# CH32V467VET-R0.net
KiCad netlist of a schematic drawn in Altium Designer
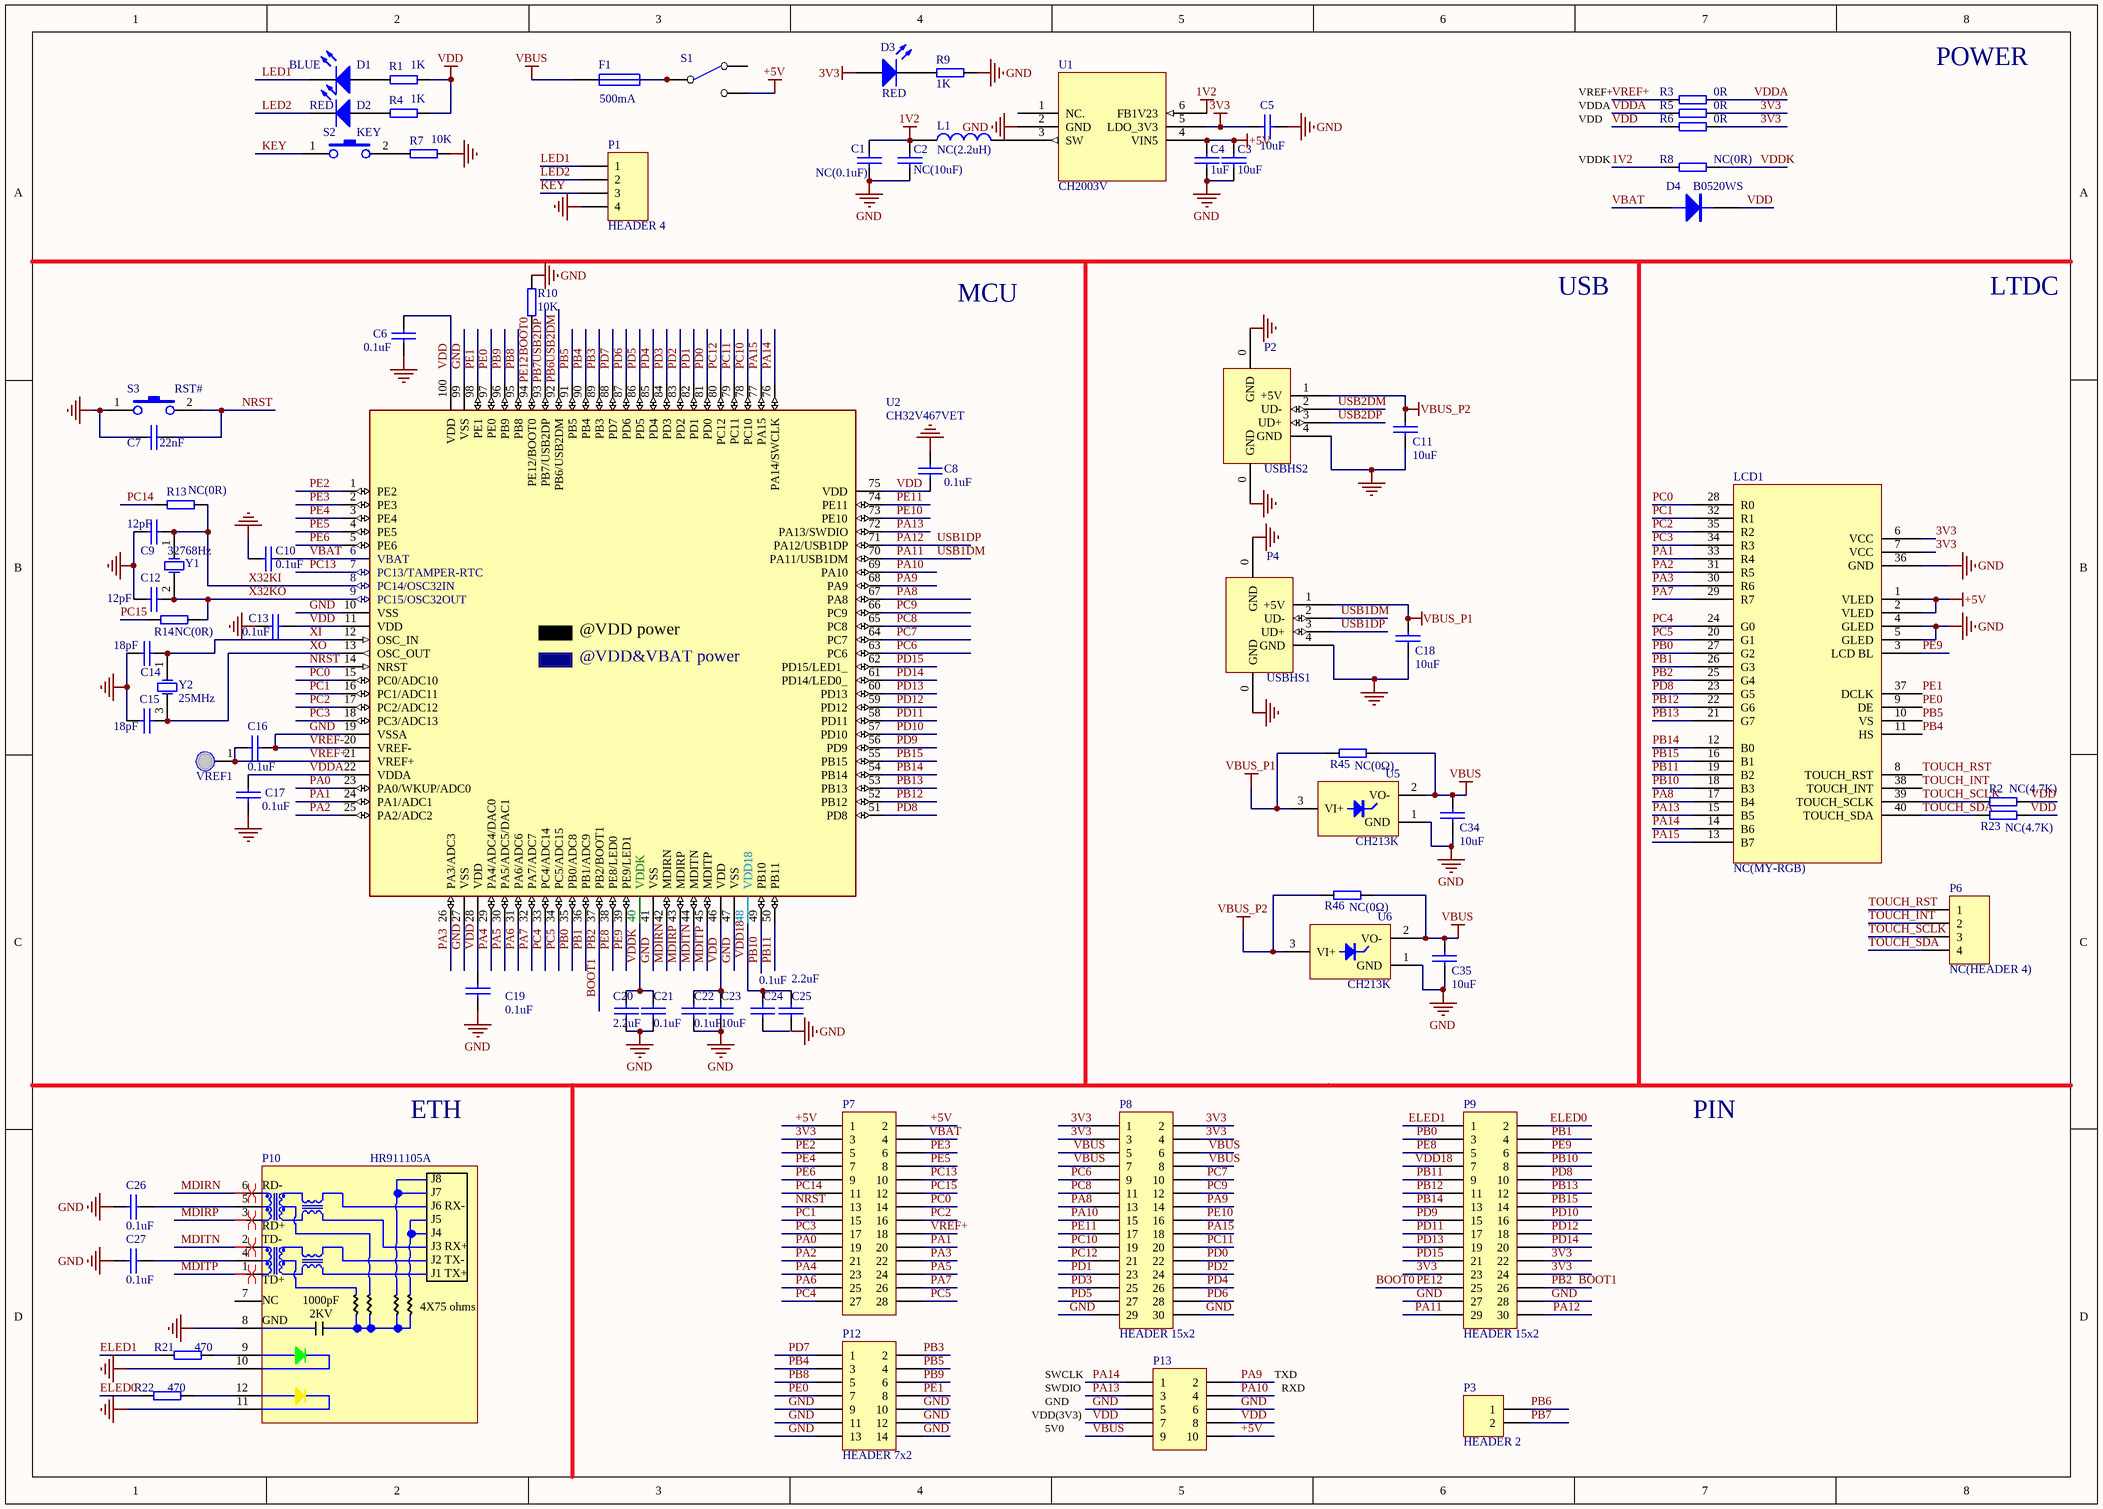
[diagram p0: CH32V467VET-R0.SchDoc]

(export (version "E")
  (design (tool "Eeschema 10.0.6"))
  (components
    (comp (ref "C1")
      (value "NC(0.1uF)")
      (footprint "0402_C")
      (description "Capacitor")
      (libsource (lib "") (part "CAP_1"))
    )
    (comp (ref "C2")
      (value "NC(10uF)")
      (footprint "0603_C")
      (description "Capacitor")
      (libsource (lib "*") (part "CAP"))
    )
    (comp (ref "C3")
      (value "10uF")
      (footprint "0603_C")
      (description "Capacitor")
      (libsource (lib "*") (part "CAP"))
    )
    (comp (ref "C4")
      (value "1uF")
      (footprint "0402_C")
      (description "Capacitor")
      (libsource (lib "") (part "CAP_1"))
    )
    (comp (ref "C5")
      (value "10uF")
      (footprint "0603_C")
      (description "Capacitor")
      (libsource (lib "*") (part "CAP"))
    )
    (comp (ref "C6")
      (value "0.1uF")
      (footprint "0402_C")
      (description "Capacitor")
      (libsource (lib "*") (part "CAP"))
    )
    (comp (ref "C7")
      (value "22nF")
      (footprint "0402_C")
      (description "Capacitor")
      (libsource (lib "") (part "CAP_2"))
    )
    (comp (ref "C8")
      (value "0.1uF")
      (footprint "0402_C")
      (description "Capacitor")
      (libsource (lib "*") (part "CAP"))
    )
    (comp (ref "C9")
      (value "12pF")
      (footprint "0402_C")
      (description "Capacitor")
      (libsource (lib "*") (part "CAP"))
    )
    (comp (ref "C10")
      (value "0.1uF")
      (footprint "0402_C")
      (description "Capacitor")
      (libsource (lib "*") (part "CAP"))
    )
    (comp (ref "C11")
      (value "10uF")
      (footprint "0603_C")
      (description "Capacitor")
      (libsource (lib "") (part "CAP_2"))
    )
    (comp (ref "C12")
      (value "12pF")
      (footprint "0402_C")
      (description "Capacitor")
      (libsource (lib "*") (part "CAP"))
    )
    (comp (ref "C13")
      (value "0.1uF")
      (footprint "0402_C")
      (description "Capacitor")
      (libsource (lib "*") (part "CAP"))
    )
    (comp (ref "C14")
      (value "18pF")
      (footprint "0402_C")
      (description "Capacitor")
      (libsource (lib "*") (part "CAP"))
    )
    (comp (ref "C15")
      (value "18pF")
      (footprint "0402_C")
      (description "Capacitor")
      (libsource (lib "*") (part "CAP"))
    )
    (comp (ref "C16")
      (value "0.1uF")
      (footprint "0402_C")
      (description "Capacitor")
      (libsource (lib "*") (part "CAP"))
    )
    (comp (ref "C17")
      (value "0.1uF")
      (footprint "0402_C")
      (description "Capacitor")
      (libsource (lib "*") (part "CAP"))
    )
    (comp (ref "C18")
      (value "10uF")
      (footprint "0603_C")
      (description "Capacitor")
      (libsource (lib "") (part "CAP_2"))
    )
    (comp (ref "C19")
      (value "0.1uF")
      (footprint "0402_C")
      (description "Capacitor")
      (libsource (lib "*") (part "CAP"))
    )
    (comp (ref "C20")
      (value "2.2uF")
      (footprint "0402_C")
      (description "Capacitor")
      (libsource (lib "*") (part "CAP"))
    )
    (comp (ref "C21")
      (value "0.1uF")
      (footprint "0402_C")
      (description "Capacitor")
      (libsource (lib "*") (part "CAP"))
    )
    (comp (ref "C22")
      (value "0.1uF")
      (footprint "0402_C")
      (description "Capacitor")
      (libsource (lib "*") (part "CAP"))
    )
    (comp (ref "C23")
      (value "10uF")
      (footprint "0402_C")
      (description "Capacitor")
      (libsource (lib "*") (part "CAP"))
    )
    (comp (ref "C24")
      (value "0.1uF")
      (footprint "0402_C")
      (description "Capacitor")
      (libsource (lib "*") (part "CAP"))
    )
    (comp (ref "C25")
      (value "2.2uF")
      (footprint "0402_C")
      (description "Capacitor")
      (libsource (lib "*") (part "CAP"))
    )
    (comp (ref "C26")
      (value "0.1uF")
      (footprint "0402_C")
      (description "Capacitor")
      (libsource (lib "wch_sch_others") (part "CAP"))
    )
    (comp (ref "C27")
      (value "0.1uF")
      (footprint "0402_C")
      (description "Capacitor")
      (libsource (lib "wch_sch_others") (part "CAP"))
    )
    (comp (ref "C34")
      (value "10uF")
      (footprint "0603_C")
      (description "Capacitor")
      (libsource (lib "") (part "CAP_2"))
    )
    (comp (ref "C35")
      (value "10uF")
      (footprint "0603_C")
      (description "Capacitor")
      (libsource (lib "") (part "CAP_2"))
    )
    (comp (ref "D1")
      (value "BLUE")
      (footprint "0603+")
      (description "Typical INFRARED GaAs LED")
      (fields (field (name "PUBLISHER") "Altium Limited"))
      (libsource (lib "*") (part "LED0"))
    )
    (comp (ref "D2")
      (value "RED")
      (footprint "0603+")
      (description "Typical INFRARED GaAs LED")
      (fields (field (name "PUBLISHER") "Altium Limited"))
      (libsource (lib "*") (part "LED0"))
    )
    (comp (ref "D3")
      (value "RED")
      (footprint "0603+")
      (description "Typical INFRARED GaAs LED")
      (fields (field (name "PUBLISHER") "Altium Limited"))
      (libsource (lib "*") (part "LED0"))
    )
    (comp (ref "D4")
      (value "B0520WS")
      (footprint "SOD-323")
      (description "Diode")
      (libsource (lib "*") (part "DIODE"))
    )
    (comp (ref "F1")
      (value "500mA")
      (footprint "0603")
      (description "Fuse")
      (libsource (lib "wch_sch_others") (part "FUSE1"))
    )
    (comp (ref "L1") (value "NC(2.2uH)") (footprint "CD32") (libsource (lib "*") (part "INDUCTOR")))
    (comp (ref "LCD1")
      (value "NC(MY-RGB)")
      (footprint "FPC40P-0.5-FK750M3")
      (libsource (lib "MY-显示") (part "MY-RGB"))
    )
    (comp (ref "P1")
      (value "HEADER 4")
      (footprint "SIP4-2.54mm")
      (description "Header, 4-Pin")
      (libsource (lib "wch_sch_others") (part "HEADER 4"))
    )
    (comp (ref "P2")
      (value "USBHS2")
      (footprint "USBAF")
      (description "USB Port")
      (libsource (lib "*") (part "USB"))
    )
    (comp (ref "P3")
      (value "HEADER 2")
      (footprint "MYPCB:SIP2-2.54mm")
      (description "Header, 2-Pin")
      (libsource (lib "wch_sch_others") (part "HEADER 2"))
    )
    (comp (ref "P4")
      (value "USBHS1")
      (footprint "USBAF")
      (description "USB Port")
      (libsource (lib "*") (part "USB"))
    )
    (comp (ref "P6")
      (value "NC(HEADER 4)")
      (footprint "SIP4-2.54mm")
      (description "Header, 4-Pin")
      (libsource (lib "wch_sch_others") (part "HEADER 4"))
    )
    (comp (ref "P7")
      (value "HEADER 14x2")
      (footprint "MYPCB:IDC28-2.54MM")
      (description "Header, 14-Pin, Dual row")
      (libsource (lib "wch_sch_others") (part "HEADER 14x2"))
    )
    (comp (ref "P8")
      (value "HEADER 15x2")
      (footprint "MYPCB:IDC30-2.54MM")
      (description "Header, 15-Pin, Dual row")
      (libsource (lib "wch_sch_others") (part "HEADER 15x2"))
    )
    (comp (ref "P9")
      (value "HEADER 15x2")
      (footprint "MYPCB:IDC30-2.54MM")
      (description "Header, 15-Pin, Dual row")
      (libsource (lib "wch_sch_others") (part "HEADER 15x2"))
    )
    (comp (ref "P10") (value "HR911105A") (footprint "HR911105A") (libsource (lib "*") (part "HR911105A")))
    (comp (ref "P12")
      (value "HEADER 7x2")
      (footprint "MYPCB:IDC14-2.54mm")
      (description "Header, 7-Pin, Dual row")
      (libsource (lib "wch_sch_others") (part "HEADER 7x2"))
    )
    (comp (ref "P13")
      (value "LINK")
      (footprint "IDC10-2.54mm")
      (description "Header, 5-Pin, Dual row, Right Angle")
      (fields (field (name "PUBLISHER") "Altium Limited"))
      (libsource (lib "Miscellaneous Connectors") (part "Header 5X2H"))
    )
    (comp (ref "R1") (value "1K") (footprint "0402") (libsource (lib "wch_sch_others") (part "RES")))
    (comp (ref "R2") (value "NC(4.7K)") (footprint "0402") (libsource (lib "wch_sch_others") (part "RES")))
    (comp (ref "R3") (value "0R") (footprint "0402") (libsource (lib "*") (part "R")))
    (comp (ref "R4") (value "1K") (footprint "0402") (libsource (lib "wch_sch_others") (part "RES")))
    (comp (ref "R5") (value "0R") (footprint "0402") (libsource (lib "*") (part "R")))
    (comp (ref "R6") (value "0R") (footprint "0402") (libsource (lib "*") (part "R")))
    (comp (ref "R7") (value "10K") (footprint "0402") (libsource (lib "wch_sch_others") (part "RES")))
    (comp (ref "R8") (value "NC(0R)") (footprint "0402") (libsource (lib "*") (part "R")))
    (comp (ref "R9") (value "1K") (footprint "0402") (libsource (lib "wch_sch_others") (part "RES")))
    (comp (ref "R10") (value "10K") (footprint "0402") (libsource (lib "wch_sch_others") (part "RES")))
    (comp (ref "R13") (value "NC(0R)") (footprint "0402") (libsource (lib "wch_sch_others") (part "RES")))
    (comp (ref "R14") (value "NC(0R)") (footprint "0402") (libsource (lib "wch_sch_others") (part "RES")))
    (comp (ref "R21") (value "470") (footprint "0402") (libsource (lib "wch_sch_others") (part "RES")))
    (comp (ref "R22") (value "470") (footprint "0402") (libsource (lib "wch_sch_others") (part "RES")))
    (comp (ref "R23") (value "NC(4.7K)") (footprint "0402") (libsource (lib "wch_sch_others") (part "RES")))
    (comp (ref "R45") (value "NC(0Ω)") (footprint "0402") (libsource (lib "wch_sch_others") (part "RES")))
    (comp (ref "R46") (value "NC(0Ω)") (footprint "0402") (libsource (lib "wch_sch_others") (part "RES")))
    (comp (ref "S1") (value "SW SPDT") (footprint "SW1") (libsource (lib "*") (part "SW SPDT")))
    (comp (ref "S2")
      (value "KEY")
      (footprint "SMD_6.1x3.65x2.5mm-KEY")
      (libsource (lib "wch_sch_others") (part "KEY1"))
    )
    (comp (ref "S3")
      (value "RST#")
      (footprint "SMD_6.1x3.65x2.5mm-KEY")
      (libsource (lib "wch_sch_others") (part "KEY1"))
    )
    (comp (ref "U1")
      (value "CH2003V")
      (footprint "SOT-23-6")
      (description "Step-Down DC-DC Converter, 5V input, 1.23V * 800mA output, with LDO 3.3V * 200mA")
      (libsource (lib "CHXXX") (part "CH2003V"))
    )
    (comp (ref "U2")
      (value "CH32V467VET")
      (footprint "LQFP100")
      (description "RISC-V FPU HD-MCU, 175MHz, USB_480M, 100M Ethernet & Phy, CAN, DVP, ADC, DAC, SRAM")
      (libsource (lib "CHXXX") (part "CH32V467VET"))
    )
    (comp (ref "U5")
      (value "CH213K")
      (footprint "SOT-23-3")
      (description "Ideal Diode 5V*1A")
      (libsource (lib "*") (part "CH213K"))
    )
    (comp (ref "U6")
      (value "CH213K")
      (footprint "SOT-23-3")
      (description "Ideal Diode 5V*1A")
      (libsource (lib "*") (part "CH213K"))
    )
    (comp (ref "VREF1")
      (value "PAD")
      (footprint "TESTPOINT1")
      (description "焊盘")
      (libsource (lib "wch_sch_others") (part "PAD"))
    )
    (comp (ref "Y1")
      (value "32768Hz")
      (footprint "FC-135")
      (description "Crystal Oscillator")
      (fields (field (name "PUBLISHER") "Altium Limited"))
      (libsource (lib "*") (part "XTAL"))
    )
    (comp (ref "Y2")
      (value "25MHz")
      (footprint "XT3225")
      (description "Crystal Oscillator")
      (fields (field (name "PUBLISHER") "Altium Limited"))
      (libsource (lib "") (part "XTAL_1"))
    )
  )
  (nets
    (net (code "1") (name "+5V") (class "Default")
      (node (ref "C3") (pin "2") (pinfunction "2_2") (pintype "passive"))
      (node (ref "C4") (pin "2") (pinfunction "2_2") (pintype "passive"))
      (node (ref "LCD1") (pin "1") (pinfunction "VLED_1") (pintype "passive"))
      (node (ref "LCD1") (pin "2") (pinfunction "VLED_2") (pintype "passive"))
      (node (ref "P13") (pin "10") (pinfunction "10_10") (pintype "passive"))
      (node (ref "P7") (pin "1") (pinfunction "1_1") (pintype "passive"))
      (node (ref "P7") (pin "2") (pinfunction "2_2") (pintype "passive"))
      (node (ref "S1") (pin "2") (pinfunction "NC_2") (pintype "passive"))
      (node (ref "U1") (pin "4") (pinfunction "VIN5_4") (pintype "power_in"))
    )
    (net (code "3") (name "/BOOT0") (class "Default")
      (node (ref "P9") (pin "25") (pinfunction "25_25") (pintype "passive"))
      (node (ref "R10") (pin "2") (pintype "passive"))
      (node (ref "U2") (pin "94") (pinfunction "PE12/BOOT0_94") (pintype "bidirectional"))
    )
    (net (code "4") (name "/BOOT1") (class "Default")
      (node (ref "LCD1") (pin "25") (pinfunction "G4_25") (pintype "passive"))
      (node (ref "P9") (pin "26") (pinfunction "26_26") (pintype "passive"))
      (node (ref "U2") (pin "37") (pinfunction "PB2/BOOT1_37") (pintype "bidirectional"))
    )
    (net (code "5") (name "/ELED0") (class "Default")
      (node (ref "P9") (pin "2") (pinfunction "2_2") (pintype "passive"))
      (node (ref "R22") (pin "1") (pintype "passive"))
    )
    (net (code "6") (name "/ELED1") (class "Default")
      (node (ref "P9") (pin "1") (pinfunction "1_1") (pintype "passive"))
      (node (ref "R21") (pin "1") (pintype "passive"))
    )
    (net (code "7") (name "/KEY") (class "Default")
      (node (ref "P1") (pin "3") (pinfunction "3_3") (pintype "passive"))
      (node (ref "S2") (pin "1") (pinfunction "1_1") (pintype "passive"))
    )
    (net (code "8") (name "/LED1") (class "Default")
      (node (ref "D1") (pin "2") (pinfunction "K_2") (pintype "passive"))
      (node (ref "P1") (pin "1") (pinfunction "1_1") (pintype "passive"))
    )
    (net (code "9") (name "/LED2") (class "Default")
      (node (ref "D2") (pin "2") (pinfunction "K_2") (pintype "passive"))
      (node (ref "P1") (pin "2") (pinfunction "2_2") (pintype "passive"))
    )
    (net (code "10") (name "/MDIRN") (class "Default")
      (node (ref "P10") (pin "6") (pintype "passive"))
      (node (ref "U2") (pin "42") (pinfunction "MDIRN_42") (pintype "bidirectional"))
    )
    (net (code "11") (name "/MDIRP") (class "Default")
      (node (ref "P10") (pin "3") (pintype "passive"))
      (node (ref "U2") (pin "43") (pinfunction "MDIRP_43") (pintype "bidirectional"))
    )
    (net (code "12") (name "/MDITN") (class "Default")
      (node (ref "P10") (pin "2") (pintype "passive"))
      (node (ref "U2") (pin "44") (pinfunction "MDITN_44") (pintype "bidirectional"))
    )
    (net (code "13") (name "/MDITP") (class "Default")
      (node (ref "P10") (pin "1") (pintype "passive"))
      (node (ref "U2") (pin "45") (pinfunction "MDITP_45") (pintype "bidirectional"))
    )
    (net (code "14") (name "/NRST") (class "Default")
      (node (ref "C7") (pin "2") (pinfunction "2_2") (pintype "passive"))
      (node (ref "P7") (pin "13") (pinfunction "13_13") (pintype "passive"))
      (node (ref "S3") (pin "2") (pinfunction "2_2") (pintype "passive"))
      (node (ref "U2") (pin "14") (pinfunction "NRST_14") (pintype "input"))
    )
    (net (code "15") (name "/PA0") (class "Default")
      (node (ref "P7") (pin "19") (pinfunction "19_19") (pintype "passive"))
      (node (ref "U2") (pin "23") (pinfunction "PA0/WKUP/ADC0_23") (pintype "bidirectional"))
    )
    (net (code "16") (name "/PA1") (class "Default")
      (node (ref "LCD1") (pin "33") (pinfunction "R4_33") (pintype "passive"))
      (node (ref "P7") (pin "20") (pinfunction "20_20") (pintype "passive"))
      (node (ref "U2") (pin "24") (pinfunction "PA1/ADC1_24") (pintype "bidirectional"))
    )
    (net (code "17") (name "/PA2") (class "Default")
      (node (ref "LCD1") (pin "31") (pinfunction "R5_31") (pintype "passive"))
      (node (ref "P7") (pin "21") (pinfunction "21_21") (pintype "passive"))
      (node (ref "U2") (pin "25") (pinfunction "PA2/ADC2_25") (pintype "bidirectional"))
    )
    (net (code "18") (name "/PA3") (class "Default")
      (node (ref "LCD1") (pin "30") (pinfunction "R6_30") (pintype "passive"))
      (node (ref "P7") (pin "22") (pinfunction "22_22") (pintype "passive"))
      (node (ref "U2") (pin "26") (pinfunction "PA3/ADC3_26") (pintype "bidirectional"))
    )
    (net (code "19") (name "/PA4") (class "Default")
      (node (ref "P7") (pin "23") (pinfunction "23_23") (pintype "passive"))
      (node (ref "U2") (pin "29") (pinfunction "PA4/ADC4/DAC0_29") (pintype "bidirectional"))
    )
    (net (code "20") (name "/PA5") (class "Default")
      (node (ref "P7") (pin "24") (pinfunction "24_24") (pintype "passive"))
      (node (ref "U2") (pin "30") (pinfunction "PA5/ADC5/DAC1_30") (pintype "bidirectional"))
    )
    (net (code "21") (name "/PA6") (class "Default")
      (node (ref "P7") (pin "25") (pinfunction "25_25") (pintype "passive"))
      (node (ref "U2") (pin "31") (pinfunction "PA6/ADC6_31") (pintype "bidirectional"))
    )
    (net (code "22") (name "/PA7") (class "Default")
      (node (ref "LCD1") (pin "29") (pinfunction "R7_29") (pintype "passive"))
      (node (ref "P7") (pin "26") (pinfunction "26_26") (pintype "passive"))
      (node (ref "U2") (pin "32") (pinfunction "PA7/ADC7_32") (pintype "bidirectional"))
    )
    (net (code "23") (name "/PA8") (class "Default")
      (node (ref "LCD1") (pin "17") (pinfunction "B4_17") (pintype "passive"))
      (node (ref "P8") (pin "13") (pinfunction "13_13") (pintype "passive"))
      (node (ref "U2") (pin "67") (pinfunction "PA8_67") (pintype "bidirectional"))
    )
    (net (code "24") (name "/PA9") (class "Default")
      (node (ref "P13") (pin "2") (pinfunction "2_2") (pintype "passive"))
      (node (ref "P8") (pin "14") (pinfunction "14_14") (pintype "passive"))
      (node (ref "U2") (pin "68") (pinfunction "PA9_68") (pintype "bidirectional"))
    )
    (net (code "25") (name "/PA10") (class "Default")
      (node (ref "P13") (pin "4") (pinfunction "4_4") (pintype "passive"))
      (node (ref "P8") (pin "15") (pinfunction "15_15") (pintype "passive"))
      (node (ref "U2") (pin "69") (pinfunction "PA10_69") (pintype "bidirectional"))
    )
    (net (code "26") (name "/PA11") (class "Default")
      (node (ref "P4") (pin "2") (pinfunction "UD-_2") (pintype "bidirectional"))
      (node (ref "P9") (pin "29") (pinfunction "29_29") (pintype "passive"))
      (node (ref "U2") (pin "70") (pinfunction "PA11/USB1DM_70") (pintype "bidirectional"))
    )
    (net (code "27") (name "/PA12") (class "Default")
      (node (ref "P4") (pin "3") (pinfunction "UD+_3") (pintype "bidirectional"))
      (node (ref "P9") (pin "30") (pinfunction "30_30") (pintype "passive"))
      (node (ref "U2") (pin "71") (pinfunction "PA12/USB1DP_71") (pintype "bidirectional"))
    )
    (net (code "28") (name "/PA13") (class "Default")
      (node (ref "LCD1") (pin "15") (pinfunction "B5_15") (pintype "passive"))
      (node (ref "P13") (pin "3") (pinfunction "3_3") (pintype "passive"))
      (node (ref "U2") (pin "72") (pinfunction "PA13/SWDIO_72") (pintype "bidirectional"))
    )
    (net (code "29") (name "/PA14") (class "Default")
      (node (ref "LCD1") (pin "14") (pinfunction "B6_14") (pintype "passive"))
      (node (ref "P13") (pin "1") (pinfunction "1_1") (pintype "passive"))
      (node (ref "U2") (pin "76") (pinfunction "PA14/SWCLK_76") (pintype "bidirectional"))
    )
    (net (code "30") (name "/PA15") (class "Default")
      (node (ref "LCD1") (pin "13") (pinfunction "B7_13") (pintype "passive"))
      (node (ref "P8") (pin "18") (pinfunction "18_18") (pintype "passive"))
      (node (ref "U2") (pin "77") (pinfunction "PA15_77") (pintype "bidirectional"))
    )
    (net (code "31") (name "/PB0") (class "Default")
      (node (ref "LCD1") (pin "27") (pinfunction "G2_27") (pintype "passive"))
      (node (ref "P9") (pin "3") (pinfunction "3_3") (pintype "passive"))
      (node (ref "U2") (pin "35") (pinfunction "PB0/ADC8_35") (pintype "bidirectional"))
    )
    (net (code "32") (name "/PB1") (class "Default")
      (node (ref "LCD1") (pin "26") (pinfunction "G3_26") (pintype "passive"))
      (node (ref "P9") (pin "4") (pinfunction "4_4") (pintype "passive"))
      (node (ref "U2") (pin "36") (pinfunction "PB1/ADC9_36") (pintype "bidirectional"))
    )
    (net (code "33") (name "/PB3") (class "Default")
      (node (ref "P12") (pin "2") (pinfunction "2_2") (pintype "passive"))
      (node (ref "U2") (pin "89") (pinfunction "PB3_89") (pintype "bidirectional"))
    )
    (net (code "34") (name "/PB4") (class "Default")
      (node (ref "LCD1") (pin "11") (pinfunction "HS_11") (pintype "passive"))
      (node (ref "P12") (pin "3") (pinfunction "3_3") (pintype "passive"))
      (node (ref "U2") (pin "90") (pinfunction "PB4_90") (pintype "bidirectional"))
    )
    (net (code "35") (name "/PB5") (class "Default")
      (node (ref "LCD1") (pin "10") (pinfunction "VS_10") (pintype "passive"))
      (node (ref "P12") (pin "4") (pinfunction "4_4") (pintype "passive"))
      (node (ref "U2") (pin "91") (pinfunction "PB5_91") (pintype "bidirectional"))
    )
    (net (code "36") (name "/PB6") (class "Default")
      (node (ref "P2") (pin "2") (pinfunction "UD-_2") (pintype "bidirectional"))
      (node (ref "P3") (pin "1") (pinfunction "1_1") (pintype "passive"))
      (node (ref "U2") (pin "92") (pinfunction "PB6/USB2DM_92") (pintype "bidirectional"))
    )
    (net (code "37") (name "/PB7") (class "Default")
      (node (ref "P2") (pin "3") (pinfunction "UD+_3") (pintype "bidirectional"))
      (node (ref "P3") (pin "2") (pinfunction "2_2") (pintype "passive"))
      (node (ref "U2") (pin "93") (pinfunction "PB7/USB2DP_93") (pintype "bidirectional"))
    )
    (net (code "38") (name "/PB8") (class "Default")
      (node (ref "P12") (pin "5") (pinfunction "5_5") (pintype "passive"))
      (node (ref "U2") (pin "95") (pinfunction "PB8_95") (pintype "bidirectional"))
    )
    (net (code "39") (name "/PB9") (class "Default")
      (node (ref "P12") (pin "6") (pinfunction "6_6") (pintype "passive"))
      (node (ref "U2") (pin "96") (pinfunction "PB9_96") (pintype "bidirectional"))
    )
    (net (code "40") (name "/PB10") (class "Default")
      (node (ref "LCD1") (pin "18") (pinfunction "B3_18") (pintype "passive"))
      (node (ref "P9") (pin "8") (pinfunction "8_8") (pintype "passive"))
      (node (ref "U2") (pin "49") (pinfunction "PB10_49") (pintype "bidirectional"))
    )
    (net (code "41") (name "/PB11") (class "Default")
      (node (ref "LCD1") (pin "19") (pinfunction "B2_19") (pintype "passive"))
      (node (ref "P9") (pin "9") (pinfunction "9_9") (pintype "passive"))
      (node (ref "U2") (pin "50") (pinfunction "PB11_50") (pintype "bidirectional"))
    )
    (net (code "42") (name "/PB12") (class "Default")
      (node (ref "LCD1") (pin "22") (pinfunction "G6_22") (pintype "passive"))
      (node (ref "P9") (pin "11") (pinfunction "11_11") (pintype "passive"))
      (node (ref "U2") (pin "52") (pinfunction "PB12_52") (pintype "bidirectional"))
    )
    (net (code "43") (name "/PB13") (class "Default")
      (node (ref "LCD1") (pin "21") (pinfunction "G7_21") (pintype "passive"))
      (node (ref "P9") (pin "12") (pinfunction "12_12") (pintype "passive"))
      (node (ref "U2") (pin "53") (pinfunction "PB13_53") (pintype "bidirectional"))
    )
    (net (code "44") (name "/PB14") (class "Default")
      (node (ref "LCD1") (pin "12") (pinfunction "B0_12") (pintype "passive"))
      (node (ref "P9") (pin "13") (pinfunction "13_13") (pintype "passive"))
      (node (ref "U2") (pin "54") (pinfunction "PB14_54") (pintype "bidirectional"))
    )
    (net (code "45") (name "/PB15") (class "Default")
      (node (ref "LCD1") (pin "16") (pinfunction "B1_16") (pintype "passive"))
      (node (ref "P9") (pin "14") (pinfunction "14_14") (pintype "passive"))
      (node (ref "U2") (pin "55") (pinfunction "PB15_55") (pintype "bidirectional"))
    )
    (net (code "46") (name "/PC0") (class "Default")
      (node (ref "LCD1") (pin "28") (pinfunction "R0_28") (pintype "passive"))
      (node (ref "P7") (pin "14") (pinfunction "14_14") (pintype "passive"))
      (node (ref "U2") (pin "15") (pinfunction "PC0/ADC10_15") (pintype "bidirectional"))
    )
    (net (code "47") (name "/PC1") (class "Default")
      (node (ref "LCD1") (pin "32") (pinfunction "R1_32") (pintype "passive"))
      (node (ref "P7") (pin "15") (pinfunction "15_15") (pintype "passive"))
      (node (ref "U2") (pin "16") (pinfunction "PC1/ADC11_16") (pintype "bidirectional"))
    )
    (net (code "48") (name "/PC2") (class "Default")
      (node (ref "LCD1") (pin "35") (pinfunction "R2_35") (pintype "passive"))
      (node (ref "P7") (pin "16") (pinfunction "16_16") (pintype "passive"))
      (node (ref "U2") (pin "17") (pinfunction "PC2/ADC12_17") (pintype "bidirectional"))
    )
    (net (code "49") (name "/PC3") (class "Default")
      (node (ref "LCD1") (pin "34") (pinfunction "R3_34") (pintype "passive"))
      (node (ref "P7") (pin "17") (pinfunction "17_17") (pintype "passive"))
      (node (ref "U2") (pin "18") (pinfunction "PC3/ADC13_18") (pintype "bidirectional"))
    )
    (net (code "50") (name "/PC4") (class "Default")
      (node (ref "LCD1") (pin "24") (pinfunction "G0_24") (pintype "passive"))
      (node (ref "P7") (pin "27") (pinfunction "27_27") (pintype "passive"))
      (node (ref "U2") (pin "33") (pinfunction "PC4/ADC14_33") (pintype "bidirectional"))
    )
    (net (code "51") (name "/PC5") (class "Default")
      (node (ref "LCD1") (pin "20") (pinfunction "G1_20") (pintype "passive"))
      (node (ref "P7") (pin "28") (pinfunction "28_28") (pintype "passive"))
      (node (ref "U2") (pin "34") (pinfunction "PC5/ADC15_34") (pintype "bidirectional"))
    )
    (net (code "52") (name "/PC6") (class "Default")
      (node (ref "P8") (pin "9") (pinfunction "9_9") (pintype "passive"))
      (node (ref "U2") (pin "63") (pinfunction "PC6_63") (pintype "bidirectional"))
    )
    (net (code "53") (name "/PC7") (class "Default")
      (node (ref "P8") (pin "10") (pinfunction "10_10") (pintype "passive"))
      (node (ref "U2") (pin "64") (pinfunction "PC7_64") (pintype "bidirectional"))
    )
    (net (code "54") (name "/PC8") (class "Default")
      (node (ref "P8") (pin "11") (pinfunction "11_11") (pintype "passive"))
      (node (ref "U2") (pin "65") (pinfunction "PC8_65") (pintype "bidirectional"))
    )
    (net (code "55") (name "/PC9") (class "Default")
      (node (ref "P8") (pin "12") (pinfunction "12_12") (pintype "passive"))
      (node (ref "U2") (pin "66") (pinfunction "PC9_66") (pintype "bidirectional"))
    )
    (net (code "56") (name "/PC10") (class "Default")
      (node (ref "P8") (pin "19") (pinfunction "19_19") (pintype "passive"))
      (node (ref "U2") (pin "78") (pinfunction "PC10_78") (pintype "bidirectional"))
    )
    (net (code "57") (name "/PC11") (class "Default")
      (node (ref "P8") (pin "20") (pinfunction "20_20") (pintype "passive"))
      (node (ref "U2") (pin "79") (pinfunction "PC11_79") (pintype "bidirectional"))
    )
    (net (code "58") (name "/PC12") (class "Default")
      (node (ref "P8") (pin "21") (pinfunction "21_21") (pintype "passive"))
      (node (ref "U2") (pin "80") (pinfunction "PC12_80") (pintype "bidirectional"))
    )
    (net (code "59") (name "/PC13") (class "Default")
      (node (ref "P7") (pin "10") (pinfunction "10_10") (pintype "passive"))
      (node (ref "U2") (pin "7") (pinfunction "PC13/TAMPER-RTC_7") (pintype "bidirectional"))
    )
    (net (code "60") (name "/PC14") (class "Default")
      (node (ref "P7") (pin "11") (pinfunction "11_11") (pintype "passive"))
      (node (ref "R13") (pin "1") (pintype "passive"))
    )
    (net (code "61") (name "/PC15") (class "Default")
      (node (ref "P7") (pin "12") (pinfunction "12_12") (pintype "passive"))
      (node (ref "R14") (pin "1") (pintype "passive"))
    )
    (net (code "62") (name "/PD0") (class "Default")
      (node (ref "P8") (pin "22") (pinfunction "22_22") (pintype "passive"))
      (node (ref "U2") (pin "81") (pinfunction "PD0_81") (pintype "bidirectional"))
    )
    (net (code "63") (name "/PD1") (class "Default")
      (node (ref "P8") (pin "23") (pinfunction "23_23") (pintype "passive"))
      (node (ref "U2") (pin "82") (pinfunction "PD1_82") (pintype "bidirectional"))
    )
    (net (code "64") (name "/PD2") (class "Default")
      (node (ref "P8") (pin "24") (pinfunction "24_24") (pintype "passive"))
      (node (ref "U2") (pin "83") (pinfunction "PD2_83") (pintype "bidirectional"))
    )
    (net (code "65") (name "/PD3") (class "Default")
      (node (ref "P8") (pin "25") (pinfunction "25_25") (pintype "passive"))
      (node (ref "U2") (pin "84") (pinfunction "PD3_84") (pintype "bidirectional"))
    )
    (net (code "66") (name "/PD4") (class "Default")
      (node (ref "P8") (pin "26") (pinfunction "26_26") (pintype "passive"))
      (node (ref "U2") (pin "85") (pinfunction "PD4_85") (pintype "bidirectional"))
    )
    (net (code "67") (name "/PD5") (class "Default")
      (node (ref "P8") (pin "27") (pinfunction "27_27") (pintype "passive"))
      (node (ref "U2") (pin "86") (pinfunction "PD5_86") (pintype "bidirectional"))
    )
    (net (code "68") (name "/PD6") (class "Default")
      (node (ref "P8") (pin "28") (pinfunction "28_28") (pintype "passive"))
      (node (ref "U2") (pin "87") (pinfunction "PD6_87") (pintype "bidirectional"))
    )
    (net (code "69") (name "/PD7") (class "Default")
      (node (ref "P12") (pin "1") (pinfunction "1_1") (pintype "passive"))
      (node (ref "U2") (pin "88") (pinfunction "PD7_88") (pintype "bidirectional"))
    )
    (net (code "70") (name "/PD8") (class "Default")
      (node (ref "LCD1") (pin "23") (pinfunction "G5_23") (pintype "passive"))
      (node (ref "P9") (pin "10") (pinfunction "10_10") (pintype "passive"))
      (node (ref "U2") (pin "51") (pinfunction "PD8_51") (pintype "bidirectional"))
    )
    (net (code "71") (name "/PD9") (class "Default")
      (node (ref "P9") (pin "15") (pinfunction "15_15") (pintype "passive"))
      (node (ref "U2") (pin "56") (pinfunction "PD9_56") (pintype "bidirectional"))
    )
    (net (code "72") (name "/PD10") (class "Default")
      (node (ref "P9") (pin "16") (pinfunction "16_16") (pintype "passive"))
      (node (ref "U2") (pin "57") (pinfunction "PD10_57") (pintype "bidirectional"))
    )
    (net (code "73") (name "/PD11") (class "Default")
      (node (ref "P9") (pin "17") (pinfunction "17_17") (pintype "passive"))
      (node (ref "U2") (pin "58") (pinfunction "PD11_58") (pintype "bidirectional"))
    )
    (net (code "74") (name "/PD12") (class "Default")
      (node (ref "P9") (pin "18") (pinfunction "18_18") (pintype "passive"))
      (node (ref "U2") (pin "59") (pinfunction "PD12_59") (pintype "bidirectional"))
    )
    (net (code "75") (name "/PD13") (class "Default")
      (node (ref "P9") (pin "19") (pinfunction "19_19") (pintype "passive"))
      (node (ref "U2") (pin "60") (pinfunction "PD13_60") (pintype "bidirectional"))
    )
    (net (code "76") (name "/PD14") (class "Default")
      (node (ref "P9") (pin "20") (pinfunction "20_20") (pintype "passive"))
      (node (ref "U2") (pin "61") (pinfunction "PD14/LED0__61") (pintype "bidirectional"))
    )
    (net (code "77") (name "/PD15") (class "Default")
      (node (ref "P9") (pin "21") (pinfunction "21_21") (pintype "passive"))
      (node (ref "U2") (pin "62") (pinfunction "PD15/LED1__62") (pintype "bidirectional"))
    )
    (net (code "78") (name "/PE0") (class "Default")
      (node (ref "LCD1") (pin "9") (pinfunction "DE_9") (pintype "passive"))
      (node (ref "P12") (pin "7") (pinfunction "7_7") (pintype "passive"))
      (node (ref "U2") (pin "97") (pinfunction "PE0_97") (pintype "bidirectional"))
    )
    (net (code "79") (name "/PE1") (class "Default")
      (node (ref "LCD1") (pin "37") (pinfunction "DCLK_37") (pintype "passive"))
      (node (ref "P12") (pin "8") (pinfunction "8_8") (pintype "passive"))
      (node (ref "U2") (pin "98") (pinfunction "PE1_98") (pintype "bidirectional"))
    )
    (net (code "80") (name "/PE2") (class "Default")
      (node (ref "P7") (pin "5") (pinfunction "5_5") (pintype "passive"))
      (node (ref "U2") (pin "1") (pinfunction "PE2_1") (pintype "bidirectional"))
    )
    (net (code "81") (name "/PE3") (class "Default")
      (node (ref "P7") (pin "6") (pinfunction "6_6") (pintype "passive"))
      (node (ref "U2") (pin "2") (pinfunction "PE3_2") (pintype "bidirectional"))
    )
    (net (code "82") (name "/PE4") (class "Default")
      (node (ref "P7") (pin "7") (pinfunction "7_7") (pintype "passive"))
      (node (ref "U2") (pin "3") (pinfunction "PE4_3") (pintype "bidirectional"))
    )
    (net (code "83") (name "/PE5") (class "Default")
      (node (ref "P7") (pin "8") (pinfunction "8_8") (pintype "passive"))
      (node (ref "U2") (pin "4") (pinfunction "PE5_4") (pintype "bidirectional"))
    )
    (net (code "84") (name "/PE6") (class "Default")
      (node (ref "P7") (pin "9") (pinfunction "9_9") (pintype "passive"))
      (node (ref "U2") (pin "5") (pinfunction "PE6_5") (pintype "bidirectional"))
    )
    (net (code "85") (name "/PE8") (class "Default")
      (node (ref "P9") (pin "5") (pinfunction "5_5") (pintype "passive"))
      (node (ref "U2") (pin "38") (pinfunction "PE8/LED0_38") (pintype "bidirectional"))
    )
    (net (code "86") (name "/PE9") (class "Default")
      (node (ref "LCD1") (pin "3") (pinfunction "LCD_BL_3") (pintype "passive"))
      (node (ref "P9") (pin "6") (pinfunction "6_6") (pintype "passive"))
      (node (ref "U2") (pin "39") (pinfunction "PE9/LED1_39") (pintype "bidirectional"))
    )
    (net (code "87") (name "/PE10") (class "Default")
      (node (ref "P8") (pin "16") (pinfunction "16_16") (pintype "passive"))
      (node (ref "U2") (pin "73") (pinfunction "PE10_73") (pintype "bidirectional"))
    )
    (net (code "88") (name "/PE11") (class "Default")
      (node (ref "P8") (pin "17") (pinfunction "17_17") (pintype "passive"))
      (node (ref "U2") (pin "74") (pinfunction "PE11_74") (pintype "bidirectional"))
    )
    (net (code "89") (name "/TOUCH_INT") (class "Default")
      (node (ref "LCD1") (pin "38") (pinfunction "TOUCH_INT_38") (pintype "passive"))
      (node (ref "P6") (pin "2") (pinfunction "2_2") (pintype "passive"))
    )
    (net (code "90") (name "/TOUCH_RST") (class "Default")
      (node (ref "LCD1") (pin "8") (pinfunction "TOUCH_RST_8") (pintype "passive"))
      (node (ref "P6") (pin "1") (pinfunction "1_1") (pintype "passive"))
    )
    (net (code "91") (name "/TOUCH_SCLK") (class "Default")
      (node (ref "LCD1") (pin "39") (pinfunction "TOUCH_SCLK_39") (pintype "passive"))
      (node (ref "P6") (pin "3") (pinfunction "3_3") (pintype "passive"))
      (node (ref "R2") (pin "2") (pintype "passive"))
    )
    (net (code "92") (name "/TOUCH_SDA") (class "Default")
      (node (ref "LCD1") (pin "40") (pinfunction "TOUCH_SDA_40") (pintype "passive"))
      (node (ref "P6") (pin "4") (pinfunction "4_4") (pintype "passive"))
      (node (ref "R23") (pin "2") (pintype "passive"))
    )
    (net (code "93") (name "/VBAT") (class "Default")
      (node (ref "C10") (pin "2") (pinfunction "2_2") (pintype "passive"))
      (node (ref "D4") (pin "1") (pinfunction "A_1") (pintype "passive"))
      (node (ref "P7") (pin "4") (pinfunction "4_4") (pintype "passive"))
      (node (ref "U2") (pin "6") (pinfunction "VBAT_6") (pintype "power_in"))
    )
    (net (code "94") (name "/VDD18") (class "Default")
      (node (ref "C24") (pin "2") (pinfunction "2_2") (pintype "passive"))
      (node (ref "C25") (pin "2") (pinfunction "2_2") (pintype "passive"))
      (node (ref "P9") (pin "7") (pinfunction "7_7") (pintype "passive"))
      (node (ref "U2") (pin "48") (pinfunction "VDD18_48") (pintype "power_in"))
    )
    (net (code "95") (name "/VDDA") (class "Default")
      (node (ref "C17") (pin "1") (pinfunction "1_1") (pintype "passive"))
      (node (ref "R3") (pin "1") (pinfunction "1_1") (pintype "passive"))
      (node (ref "R5") (pin "2") (pinfunction "2_2") (pintype "passive"))
      (node (ref "U2") (pin "22") (pinfunction "VDDA_22") (pintype "power_in"))
    )
    (net (code "96") (name "/VDDK") (class "Default")
      (node (ref "C20") (pin "2") (pinfunction "2_2") (pintype "passive"))
      (node (ref "C21") (pin "2") (pinfunction "2_2") (pintype "passive"))
      (node (ref "R8") (pin "1") (pinfunction "1_1") (pintype "passive"))
      (node (ref "U2") (pin "40") (pinfunction "VDDK_40") (pintype "power_in"))
    )
    (net (code "97") (name "/VREF+") (class "Default")
      (node (ref "C16") (pin "1") (pinfunction "1_1") (pintype "passive"))
      (node (ref "P7") (pin "18") (pinfunction "18_18") (pintype "passive"))
      (node (ref "R3") (pin "2") (pinfunction "2_2") (pintype "passive"))
      (node (ref "U2") (pin "21") (pinfunction "VREF+_21") (pintype "power_in"))
      (node (ref "VREF1") (pin "1") (pintype "passive"))
    )
    (net (code "98") (name "/X32KI") (class "Default")
      (node (ref "C9") (pin "2") (pinfunction "2_2") (pintype "passive"))
      (node (ref "R13") (pin "2") (pintype "passive"))
      (node (ref "U2") (pin "8") (pinfunction "PC14/OSC32IN_8") (pintype "bidirectional"))
      (node (ref "Y1") (pin "1") (pinfunction "OSC1_1") (pintype "passive"))
    )
    (net (code "99") (name "/X32KO") (class "Default")
      (node (ref "C12") (pin "2") (pinfunction "2_2") (pintype "passive"))
      (node (ref "R14") (pin "2") (pintype "passive"))
      (node (ref "U2") (pin "9") (pinfunction "PC15/OSC32OUT_9") (pintype "bidirectional"))
      (node (ref "Y1") (pin "2") (pinfunction "OSC2_2") (pintype "passive"))
    )
    (net (code "100") (name "/XI") (class "Default")
      (node (ref "C14") (pin "2") (pinfunction "2_2") (pintype "passive"))
      (node (ref "U2") (pin "12") (pinfunction "OSC_IN_12") (pintype "input"))
      (node (ref "Y2") (pin "1") (pinfunction "OSC1_1") (pintype "passive"))
    )
    (net (code "101") (name "/XO") (class "Default")
      (node (ref "C15") (pin "2") (pinfunction "2_2") (pintype "passive"))
      (node (ref "U2") (pin "13") (pinfunction "OSC_OUT_13") (pintype "output"))
      (node (ref "Y2") (pin "3") (pinfunction "OSC2_3") (pintype "passive"))
    )
    (net (code "102") (name "1V2") (class "Default")
      (node (ref "C1") (pin "2") (pinfunction "2_2") (pintype "passive"))
      (node (ref "C2") (pin "2") (pinfunction "2_2") (pintype "passive"))
      (node (ref "L1") (pin "2") (pinfunction "2_2") (pintype "passive"))
      (node (ref "R8") (pin "2") (pinfunction "2_2") (pintype "passive"))
      (node (ref "U1") (pin "6") (pinfunction "FB1V23_6") (pintype "input"))
    )
    (net (code "103") (name "3V3") (class "Default")
      (node (ref "C5") (pin "2") (pinfunction "2_2") (pintype "passive"))
      (node (ref "D3") (pin "1") (pinfunction "A_1") (pintype "passive"))
      (node (ref "LCD1") (pin "6") (pinfunction "VCC_6") (pintype "passive"))
      (node (ref "LCD1") (pin "7") (pinfunction "VCC_7") (pintype "passive"))
      (node (ref "P7") (pin "3") (pinfunction "3_3") (pintype "passive"))
      (node (ref "P8") (pin "1") (pinfunction "1_1") (pintype "passive"))
      (node (ref "P8") (pin "2") (pinfunction "2_2") (pintype "passive"))
      (node (ref "P8") (pin "3") (pinfunction "3_3") (pintype "passive"))
      (node (ref "P8") (pin "4") (pinfunction "4_4") (pintype "passive"))
      (node (ref "P9") (pin "22") (pinfunction "22_22") (pintype "passive"))
      (node (ref "P9") (pin "23") (pinfunction "23_23") (pintype "passive"))
      (node (ref "P9") (pin "24") (pinfunction "24_24") (pintype "passive"))
      (node (ref "R5") (pin "1") (pinfunction "1_1") (pintype "passive"))
      (node (ref "R6") (pin "1") (pinfunction "1_1") (pintype "passive"))
      (node (ref "U1") (pin "5") (pinfunction "LDO_3V3_5") (pintype "power_in"))
    )
    (net (code "104") (name "GND") (class "Default")
      (node (ref "C1") (pin "1") (pinfunction "1_1") (pintype "passive"))
      (node (ref "C10") (pin "1") (pinfunction "1_1") (pintype "passive"))
      (node (ref "C11") (pin "2") (pinfunction "2_2") (pintype "passive"))
      (node (ref "C12") (pin "1") (pinfunction "1_1") (pintype "passive"))
      (node (ref "C13") (pin "2") (pinfunction "2_2") (pintype "passive"))
      (node (ref "C14") (pin "1") (pinfunction "1_1") (pintype "passive"))
      (node (ref "C15") (pin "1") (pinfunction "1_1") (pintype "passive"))
      (node (ref "C16") (pin "2") (pinfunction "2_2") (pintype "passive"))
      (node (ref "C17") (pin "2") (pinfunction "2_2") (pintype "passive"))
      (node (ref "C18") (pin "2") (pinfunction "2_2") (pintype "passive"))
      (node (ref "C19") (pin "1") (pinfunction "1_1") (pintype "passive"))
      (node (ref "C2") (pin "1") (pinfunction "1_1") (pintype "passive"))
      (node (ref "C20") (pin "1") (pinfunction "1_1") (pintype "passive"))
      (node (ref "C21") (pin "1") (pinfunction "1_1") (pintype "passive"))
      (node (ref "C22") (pin "1") (pinfunction "1_1") (pintype "passive"))
      (node (ref "C23") (pin "1") (pinfunction "1_1") (pintype "passive"))
      (node (ref "C25") (pin "1") (pinfunction "1_1") (pintype "passive"))
      (node (ref "C26") (pin "1") (pinfunction "1_1") (pintype "passive"))
      (node (ref "C27") (pin "1") (pinfunction "1_1") (pintype "passive"))
      (node (ref "C3") (pin "1") (pinfunction "1_1") (pintype "passive"))
      (node (ref "C34") (pin "2") (pinfunction "2_2") (pintype "passive"))
      (node (ref "C35") (pin "2") (pinfunction "2_2") (pintype "passive"))
      (node (ref "C4") (pin "1") (pinfunction "1_1") (pintype "passive"))
      (node (ref "C5") (pin "1") (pinfunction "1_1") (pintype "passive"))
      (node (ref "C6") (pin "1") (pinfunction "1_1") (pintype "passive"))
      (node (ref "C7") (pin "1") (pinfunction "1_1") (pintype "passive"))
      (node (ref "C8") (pin "2") (pinfunction "2_2") (pintype "passive"))
      (node (ref "C9") (pin "1") (pinfunction "1_1") (pintype "passive"))
      (node (ref "LCD1") (pin "36") (pinfunction "GND_36") (pintype "passive"))
      (node (ref "LCD1") (pin "4") (pinfunction "GLED_4") (pintype "passive"))
      (node (ref "LCD1") (pin "5") (pinfunction "GLED_5") (pintype "passive"))
      (node (ref "P1") (pin "4") (pinfunction "4_4") (pintype "passive"))
      (node (ref "P10") (pin "10") (pintype "passive"))
      (node (ref "P10") (pin "11") (pintype "passive"))
      (node (ref "P10") (pin "8") (pintype "passive"))
      (node (ref "P12") (pin "10") (pinfunction "10_10") (pintype "passive"))
      (node (ref "P12") (pin "11") (pinfunction "11_11") (pintype "passive"))
      (node (ref "P12") (pin "12") (pinfunction "12_12") (pintype "passive"))
      (node (ref "P12") (pin "13") (pinfunction "13_13") (pintype "passive"))
      (node (ref "P12") (pin "14") (pinfunction "14_14") (pintype "passive"))
      (node (ref "P12") (pin "9") (pinfunction "9_9") (pintype "passive"))
      (node (ref "P13") (pin "5") (pinfunction "5_5") (pintype "passive"))
      (node (ref "P13") (pin "6") (pinfunction "6_6") (pintype "passive"))
      (node (ref "P2") (pin "0") (pinfunction "GND_0") (pintype "power_in"))
      (node (ref "P2") (pin "4") (pinfunction "GND_4") (pintype "power_in"))
      (node (ref "P4") (pin "0") (pinfunction "GND_0") (pintype "power_in"))
      (node (ref "P4") (pin "4") (pinfunction "GND_4") (pintype "power_in"))
      (node (ref "P8") (pin "29") (pinfunction "29_29") (pintype "passive"))
      (node (ref "P8") (pin "30") (pinfunction "30_30") (pintype "passive"))
      (node (ref "P9") (pin "27") (pinfunction "27_27") (pintype "passive"))
      (node (ref "P9") (pin "28") (pinfunction "28_28") (pintype "passive"))
      (node (ref "R10") (pin "1") (pintype "passive"))
      (node (ref "R7") (pin "1") (pintype "passive"))
      (node (ref "R9") (pin "2") (pintype "passive"))
      (node (ref "S3") (pin "1") (pinfunction "1_1") (pintype "passive"))
      (node (ref "U1") (pin "2") (pinfunction "GND_2") (pintype "power_in"))
      (node (ref "U2") (pin "10") (pinfunction "VSS_10") (pintype "power_in"))
      (node (ref "U2") (pin "19") (pinfunction "VSSA_19") (pintype "power_in"))
      (node (ref "U2") (pin "20") (pinfunction "VREF-_20") (pintype "power_in"))
      (node (ref "U2") (pin "27") (pinfunction "VSS_27") (pintype "power_in"))
      (node (ref "U2") (pin "41") (pinfunction "VSS_41") (pintype "power_in"))
      (node (ref "U2") (pin "47") (pinfunction "VSS_47") (pintype "power_in"))
      (node (ref "U2") (pin "99") (pinfunction "VSS_99") (pintype "power_in"))
      (node (ref "U5") (pin "1") (pinfunction "GND_1") (pintype "power_in"))
      (node (ref "U6") (pin "1") (pinfunction "GND_1") (pintype "power_in"))
    )
    (net (code "105") (name "Net-(C26-Pad2)") (class "Default")
      (node (ref "C26") (pin "2") (pinfunction "2_2") (pintype "passive"))
      (node (ref "P10") (pin "5") (pintype "passive"))
    )
    (net (code "106") (name "Net-(C27-Pad2)") (class "Default")
      (node (ref "C27") (pin "2") (pinfunction "2_2") (pintype "passive"))
      (node (ref "P10") (pin "4") (pintype "passive"))
    )
    (net (code "107") (name "Net-(D1-A)") (class "Default")
      (node (ref "D1") (pin "1") (pinfunction "A_1") (pintype "passive"))
      (node (ref "R1") (pin "2") (pintype "passive"))
    )
    (net (code "108") (name "Net-(D2-A)") (class "Default")
      (node (ref "D2") (pin "1") (pinfunction "A_1") (pintype "passive"))
      (node (ref "R4") (pin "2") (pintype "passive"))
    )
    (net (code "109") (name "Net-(D3-K)") (class "Default")
      (node (ref "D3") (pin "2") (pinfunction "K_2") (pintype "passive"))
      (node (ref "R9") (pin "1") (pintype "passive"))
    )
    (net (code "110") (name "Net-(P10-Pad9)") (class "Default")
      (node (ref "P10") (pin "9") (pintype "passive"))
      (node (ref "R21") (pin "2") (pintype "passive"))
    )
    (net (code "111") (name "Net-(P10-Pad12)") (class "Default")
      (node (ref "P10") (pin "12") (pintype "passive"))
      (node (ref "R22") (pin "2") (pintype "passive"))
    )
    (net (code "112") (name "Net-(R7-Pad2)") (class "Default")
      (node (ref "R7") (pin "2") (pintype "passive"))
      (node (ref "S2") (pin "2") (pinfunction "2_2") (pintype "passive"))
    )
    (net (code "113") (name "Net-(S1-COMMON)") (class "Default")
      (node (ref "F1") (pin "2") (pinfunction "2_2") (pintype "passive"))
      (node (ref "S1") (pin "1") (pinfunction "COMMON_1") (pintype "passive"))
    )
    (net (code "114") (name "Net-(U1-SW)") (class "Default")
      (node (ref "L1") (pin "1") (pinfunction "1_1") (pintype "passive"))
      (node (ref "U1") (pin "3") (pinfunction "SW_3") (pintype "output"))
    )
    (net (code "115") (name "VBUS") (class "Default")
      (node (ref "C34") (pin "1") (pinfunction "1_1") (pintype "passive"))
      (node (ref "C35") (pin "1") (pinfunction "1_1") (pintype "passive"))
      (node (ref "F1") (pin "1") (pinfunction "1_1") (pintype "passive"))
      (node (ref "P13") (pin "9") (pinfunction "9_9") (pintype "passive"))
      (node (ref "P8") (pin "5") (pinfunction "5_5") (pintype "passive"))
      (node (ref "P8") (pin "6") (pinfunction "6_6") (pintype "passive"))
      (node (ref "P8") (pin "7") (pinfunction "7_7") (pintype "passive"))
      (node (ref "P8") (pin "8") (pinfunction "8_8") (pintype "passive"))
      (node (ref "R45") (pin "1") (pintype "passive"))
      (node (ref "R46") (pin "1") (pintype "passive"))
      (node (ref "U5") (pin "2") (pinfunction "VO-_2") (pintype "power_in"))
      (node (ref "U6") (pin "2") (pinfunction "VO-_2") (pintype "power_in"))
    )
    (net (code "116") (name "VBUS_P1") (class "Default")
      (node (ref "C18") (pin "1") (pinfunction "1_1") (pintype "passive"))
      (node (ref "P4") (pin "1") (pinfunction "+5V_1") (pintype "power_in"))
      (node (ref "R45") (pin "2") (pintype "passive"))
      (node (ref "U5") (pin "3") (pinfunction "VI+_3") (pintype "power_in"))
    )
    (net (code "117") (name "VBUS_P2") (class "Default")
      (node (ref "C11") (pin "1") (pinfunction "1_1") (pintype "passive"))
      (node (ref "P2") (pin "1") (pinfunction "+5V_1") (pintype "power_in"))
      (node (ref "R46") (pin "2") (pintype "passive"))
      (node (ref "U6") (pin "3") (pinfunction "VI+_3") (pintype "power_in"))
    )
    (net (code "118") (name "VDD") (class "Default")
      (node (ref "C13") (pin "1") (pinfunction "1_1") (pintype "passive"))
      (node (ref "C19") (pin "2") (pinfunction "2_2") (pintype "passive"))
      (node (ref "C22") (pin "2") (pinfunction "2_2") (pintype "passive"))
      (node (ref "C23") (pin "2") (pinfunction "2_2") (pintype "passive"))
      (node (ref "C6") (pin "2") (pinfunction "2_2") (pintype "passive"))
      (node (ref "C8") (pin "1") (pinfunction "1_1") (pintype "passive"))
      (node (ref "D4") (pin "2") (pinfunction "K_2") (pintype "passive"))
      (node (ref "P13") (pin "7") (pinfunction "7_7") (pintype "passive"))
      (node (ref "P13") (pin "8") (pinfunction "8_8") (pintype "passive"))
      (node (ref "R1") (pin "1") (pintype "passive"))
      (node (ref "R2") (pin "1") (pintype "passive"))
      (node (ref "R23") (pin "1") (pintype "passive"))
      (node (ref "R4") (pin "1") (pintype "passive"))
      (node (ref "R6") (pin "2") (pinfunction "2_2") (pintype "passive"))
      (node (ref "U2") (pin "100") (pinfunction "VDD_100") (pintype "power_in"))
      (node (ref "U2") (pin "11") (pinfunction "VDD_11") (pintype "power_in"))
      (node (ref "U2") (pin "28") (pinfunction "VDD_28") (pintype "power_in"))
      (node (ref "U2") (pin "46") (pinfunction "VDD_46") (pintype "power_in"))
      (node (ref "U2") (pin "75") (pinfunction "VDD_75") (pintype "power_in"))
    )
    (net (code "119") (name "unconnected-(C24-Pad1)") (class "Default")
      (node (ref "C24") (pin "1") (pinfunction "1_1") (pintype "passive"))
    )
    (net (code "120") (name "unconnected-(P10-Pad7)") (class "Default")
      (node (ref "P10") (pin "7") (pintype "passive"))
    )
    (net (code "121") (name "unconnected-(S1-NO-Pad3)") (class "Default")
      (node (ref "S1") (pin "3") (pinfunction "NO_3") (pintype "passive"))
    )
    (net (code "122") (name "unconnected-(U1-NC.-Pad1)") (class "Default")
      (node (ref "U1") (pin "1") (pinfunction "NC._1") (pintype "passive"))
    )
  )
)
